# LV_power.net
KiCad netlist of a schematic drawn in Altium Designer
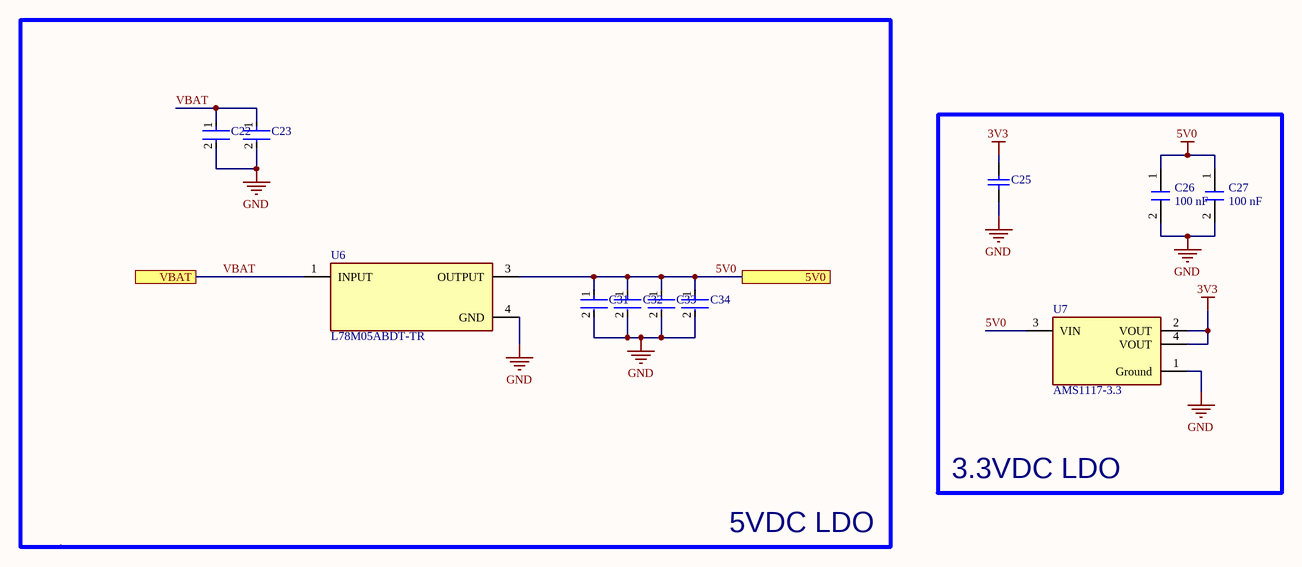
[diagram p0: LV_power.SchDoc]

(export (version "E")
  (design (tool "Eeschema 10.0.6"))
  (components
    (comp (ref "C22")
      (value "CC0805MKX5R8BB226")
      (footprint "FP-CC0805-0_2-1_45-IPC_C")
      (description "CAP CER 22UF 25V X5R 0805")
      (fields (field (name "TOLERANCE") "20%"))
      (libsource (lib "Altium Content Vault") (part "11868f565c42a9108669ba33697ecf6"))
    )
    (comp (ref "C23")
      (value "CC0805MKX5R8BB226")
      (footprint "FP-CC0805-0_2-1_45-IPC_C")
      (description "CAP CER 22UF 25V X5R 0805")
      (fields (field (name "TOLERANCE") "20%"))
      (libsource (lib "Altium Content Vault") (part "11868f565c42a9108669ba33697ecf6"))
    )
    (comp (ref "C25")
      (value "0805ZG106ZAT2A")
      (footprint "CAPC2013X152X50NL20T25")
      (fields (field (name "MANUFACTURER") "AVX Interconnect / Elco"))
      (libsource (lib "Altium Content Vault") (part "CAP"))
    )
    (comp (ref "C26")
      (value "100 nF")
      (footprint "0603_FP")
      (fields (field (name "Comment") "Capacitor_0603"))
      (libsource (lib "RC_sch") (part "Capacitor_0603"))
    )
    (comp (ref "C27")
      (value "100 nF")
      (footprint "0603_FP")
      (fields (field (name "Comment") "Capacitor_0603"))
      (libsource (lib "RC_sch") (part "Capacitor_0603"))
    )
    (comp (ref "C31")
      (value "GRM21BR61A476ME15K")
      (footprint "FP-GRM21B-0_2-e0_2_0_7-IPC_B")
      (description "Chip Multilayer Ceramic Capacitors for General Purpose, 0805, 47uF, X5R, 15%, 20%, 10V")
      (fields (field (name "TOLERANCE") "20%"))
      (libsource (lib "Altium Content Vault") (part "b4654b650e69147ec39a6b967a45e02"))
    )
    (comp (ref "C32")
      (value "GRM21BR61A476ME15K")
      (footprint "FP-GRM21B-0_2-e0_2_0_7-IPC_B")
      (description "Chip Multilayer Ceramic Capacitors for General Purpose, 0805, 47uF, X5R, 15%, 20%, 10V")
      (fields (field (name "TOLERANCE") "20%"))
      (libsource (lib "Altium Content Vault") (part "b4654b650e69147ec39a6b967a45e02"))
    )
    (comp (ref "C33")
      (value "GRM21BR61A476ME15K")
      (footprint "FP-GRM21B-0_2-e0_2_0_7-IPC_B")
      (description "Chip Multilayer Ceramic Capacitors for General Purpose, 0805, 47uF, X5R, 15%, 20%, 10V")
      (fields (field (name "TOLERANCE") "20%"))
      (libsource (lib "Altium Content Vault") (part "b4654b650e69147ec39a6b967a45e02"))
    )
    (comp (ref "C34")
      (value "GRM21BR61A476ME15K")
      (footprint "FP-GRM21B-0_2-e0_2_0_7-IPC_B")
      (description "Chip Multilayer Ceramic Capacitors for General Purpose, 0805, 47uF, X5R, 15%, 20%, 10V")
      (fields (field (name "TOLERANCE") "20%"))
      (libsource (lib "Altium Content Vault") (part "b4654b650e69147ec39a6b967a45e02"))
    )
    (comp (ref "U6")
      (value "L78M05ABDT-TR")
      (footprint "FP-L78M05ABDT-TR-MFG")
      (description "IC REG LINEAR 5V 500MA DPAK")
      (fields (field (name "TOLERANCE") "4%"))
      (libsource (lib "Altium Content Vault") (part "9f44cecb34f7d82ec50de3d0489c717"))
    )
    (comp (ref "U7")
      (value "AMS1117-3.3")
      (footprint "FP-AMS1117-IPC_C")
      (description "LDO Voltage Regulators 1A, 3.3V")
      (fields
        (field (name "OCTOPART") "https://octopart.com/ams1117-3.3-advanced+monolithic+systems-25899300")
        (field (name "MANUFACTURER") "Advanced Monolithic Systems")
      )
      (libsource (lib "Altium Content Vault") (part "8bdbb5f8e77002000e30dd2845d0354"))
    )
  )
  (nets
    (net (code "1") (name "/VBAT") (class "Default")
      (node (ref "C22") (pin "1") (pinfunction "1_1") (pintype "passive"))
      (node (ref "C23") (pin "1") (pinfunction "1_1") (pintype "passive"))
      (node (ref "U6") (pin "1") (pinfunction "INPUT_1") (pintype "power_in"))
    )
    (net (code "2") (name "3V3") (class "Default")
      (node (ref "C25") (pin "2") (pinfunction "2_2") (pintype "passive"))
      (node (ref "U7") (pin "2") (pinfunction "VOUT_2") (pintype "passive"))
      (node (ref "U7") (pin "4") (pinfunction "VOUT_4") (pintype "passive"))
    )
    (net (code "3") (name "5V0") (class "Default")
      (node (ref "C26") (pin "1") (pinfunction "1_1") (pintype "passive"))
      (node (ref "C27") (pin "1") (pinfunction "1_1") (pintype "passive"))
      (node (ref "C31") (pin "1") (pinfunction "1_1") (pintype "passive"))
      (node (ref "C32") (pin "1") (pinfunction "1_1") (pintype "passive"))
      (node (ref "C33") (pin "1") (pinfunction "1_1") (pintype "passive"))
      (node (ref "C34") (pin "1") (pinfunction "1_1") (pintype "passive"))
      (node (ref "U6") (pin "3") (pinfunction "OUTPUT_3") (pintype "power_in"))
      (node (ref "U7") (pin "3") (pinfunction "VIN_3") (pintype "power_in"))
    )
    (net (code "4") (name "GND") (class "Default")
      (node (ref "C22") (pin "2") (pinfunction "2_2") (pintype "passive"))
      (node (ref "C23") (pin "2") (pinfunction "2_2") (pintype "passive"))
      (node (ref "C25") (pin "1") (pinfunction "1_1") (pintype "passive"))
      (node (ref "C26") (pin "2") (pinfunction "2_2") (pintype "passive"))
      (node (ref "C27") (pin "2") (pinfunction "2_2") (pintype "passive"))
      (node (ref "C31") (pin "2") (pinfunction "2_2") (pintype "passive"))
      (node (ref "C32") (pin "2") (pinfunction "2_2") (pintype "passive"))
      (node (ref "C33") (pin "2") (pinfunction "2_2") (pintype "passive"))
      (node (ref "C34") (pin "2") (pinfunction "2_2") (pintype "passive"))
      (node (ref "U6") (pin "4") (pinfunction "GND_4") (pintype "power_in"))
      (node (ref "U7") (pin "1") (pinfunction "Ground_1") (pintype "power_in"))
    )
  )
)
